# AFE.net
KiCad netlist of a schematic drawn in Altium Designer
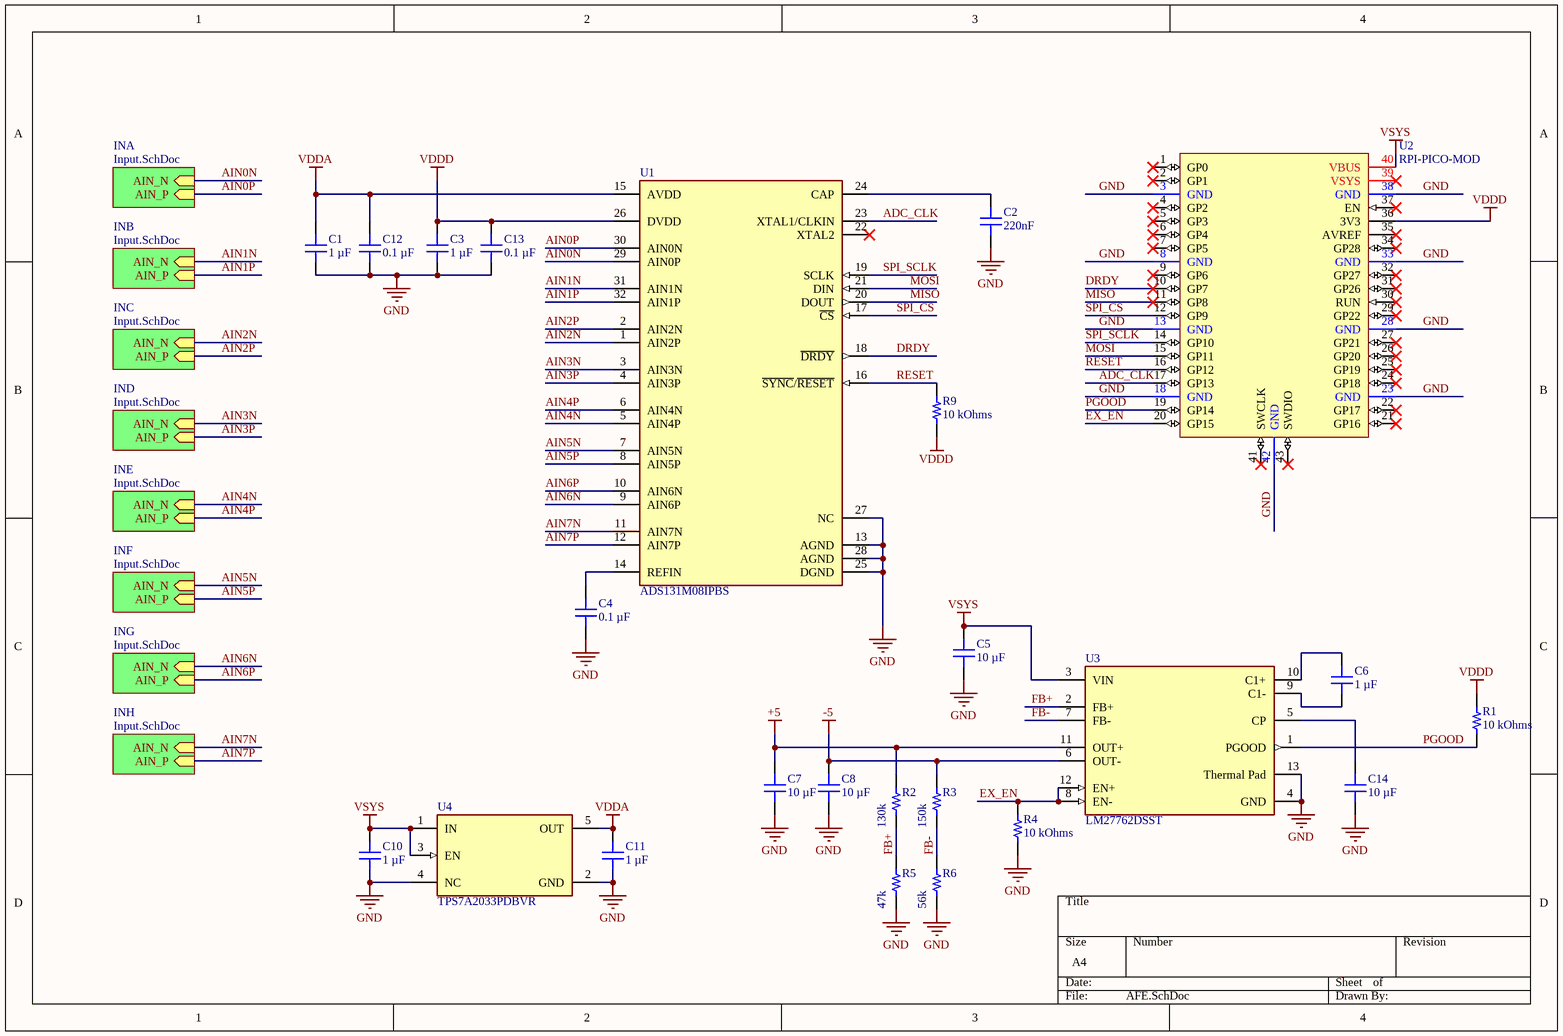
[diagram p0: AFE.SchDoc]

(export (version "E")
  (design (tool "Eeschema 10.0.6"))
  (components
    (comp (ref "C1")
      (value "1 µF")
      (footprint "CAP 0603_1608")
      (description "CAP CER 1UF 16V X7R 0603")
      (fields
        (field (name "PART NUMBER") "C0603C105K4RACAUTO")
        (field (name "CAPACITANCE") "1 µF")
        (field (name "MANUFACTURER") "KEMET")
      )
      (libsource (lib "Celestial Altium Library - altium_library") (part "Capacitor"))
    )
    (comp (ref "C2")
      (value "0.22 µF")
      (footprint "CAP 0603_1608")
      (description "CAP CER 0.22UF 50V X7R 0603")
      (fields
        (field (name "PART NUMBER") "0603BB224K500YT")
        (field (name "CAPACITANCE") "220nF")
        (field (name "MANUFACTURER") "Knowles Novacap")
      )
      (libsource (lib "Celestial Altium Library - altium_library") (part "Capacitor"))
    )
    (comp (ref "C3")
      (value "1 µF")
      (footprint "CAP 0603_1608")
      (description "CAP CER 1UF 16V X7R 0603")
      (fields
        (field (name "PART NUMBER") "C0603C105K4RACAUTO")
        (field (name "CAPACITANCE") "1 µF")
        (field (name "MANUFACTURER") "KEMET")
      )
      (libsource (lib "Celestial Altium Library - altium_library") (part "Capacitor"))
    )
    (comp (ref "C4")
      (value "0.1 µF")
      (footprint "CAP 0603_1608")
      (description "CAP CER 0.1UF 50V X7R 0603")
      (fields
        (field (name "PART NUMBER") "C0603C104K5RAC7411")
        (field (name "CAPACITANCE") "0.1 µF")
        (field (name "MANUFACTURER") "KEMET")
      )
      (libsource (lib "Celestial Altium Library - altium_library") (part "Capacitor"))
    )
    (comp (ref "C5")
      (value "10 µF")
      (footprint "CAP 0805_2012")
      (description "CAP CER 10UF 10V X7S 0805")
      (fields
        (field (name "PART NUMBER") "CL21Y106KPQVPNE")
        (field (name "CAPACITANCE") "10 µF")
        (field (name "MANUFACTURER") "Samsung Electro-Mechanics")
      )
      (libsource (lib "Celestial Altium Library - altium_library") (part "Capacitor"))
    )
    (comp (ref "C6")
      (value "1 µF")
      (footprint "CAP 0603_1608")
      (description "CAP CER 1UF 10V X7R 0603")
      (fields
        (field (name "PART NUMBER") "CC0603KRX7R6BB105")
        (field (name "CAPACITANCE") "1 µF")
        (field (name "MANUFACTURER") "Yageo")
      )
      (libsource (lib "Celestial Altium Library - altium_library") (part "Capacitor"))
    )
    (comp (ref "C7")
      (value "10 µF")
      (footprint "CAP 0805_2012")
      (description "CAP CER 10UF 10V X7S 0805")
      (fields
        (field (name "PART NUMBER") "CL21Y106KPQVPNE")
        (field (name "CAPACITANCE") "10 µF")
        (field (name "MANUFACTURER") "Samsung Electro-Mechanics")
      )
      (libsource (lib "Celestial Altium Library - altium_library") (part "Capacitor"))
    )
    (comp (ref "C8")
      (value "10 µF")
      (footprint "CAP 0805_2012")
      (description "CAP CER 10UF 10V X7S 0805")
      (fields
        (field (name "PART NUMBER") "CL21Y106KPQVPNE")
        (field (name "CAPACITANCE") "10 µF")
        (field (name "MANUFACTURER") "Samsung Electro-Mechanics")
      )
      (libsource (lib "Celestial Altium Library - altium_library") (part "Capacitor"))
    )
    (comp (ref "C10")
      (value "1 µF")
      (footprint "CAP 0603_1608")
      (description "CAP CER 1UF 16V X7R 0603")
      (fields
        (field (name "PART NUMBER") "C0603C105K4RACAUTO")
        (field (name "CAPACITANCE") "1 µF")
        (field (name "MANUFACTURER") "KEMET")
      )
      (libsource (lib "Celestial Altium Library - altium_library") (part "Capacitor"))
    )
    (comp (ref "C11")
      (value "1 µF")
      (footprint "CAP 0603_1608")
      (description "CAP CER 1UF 16V X7R 0603")
      (fields
        (field (name "PART NUMBER") "C0603C105K4RACAUTO")
        (field (name "CAPACITANCE") "1 µF")
        (field (name "MANUFACTURER") "KEMET")
      )
      (libsource (lib "Celestial Altium Library - altium_library") (part "Capacitor"))
    )
    (comp (ref "C12")
      (value "0.1 µF")
      (footprint "CAP 0603_1608")
      (description "CAP CER 0.1UF 50V X7R 0603")
      (fields
        (field (name "PART NUMBER") "C0603C104K5RAC7411")
        (field (name "CAPACITANCE") "0.1 µF")
        (field (name "MANUFACTURER") "KEMET")
      )
      (libsource (lib "Celestial Altium Library - altium_library") (part "Capacitor"))
    )
    (comp (ref "C13")
      (value "0.1 µF")
      (footprint "CAP 0603_1608")
      (description "CAP CER 0.1UF 50V X7R 0603")
      (fields
        (field (name "PART NUMBER") "C0603C104K5RAC7411")
        (field (name "CAPACITANCE") "0.1 µF")
        (field (name "MANUFACTURER") "KEMET")
      )
      (libsource (lib "Celestial Altium Library - altium_library") (part "Capacitor"))
    )
    (comp (ref "C14")
      (value "10 µF")
      (footprint "CAP 0805_2012")
      (description "CAP CER 10UF 10V X7S 0805")
      (fields
        (field (name "PART NUMBER") "CL21Y106KPQVPNE")
        (field (name "CAPACITANCE") "10 µF")
        (field (name "MANUFACTURER") "Samsung Electro-Mechanics")
      )
      (libsource (lib "Celestial Altium Library - altium_library") (part "Capacitor"))
    )
    (comp (ref "R1")
      (value "10 kOhms")
      (footprint "RES 0603_1608")
      (description "RES 10K OHM 0.1% 1/16W 0603")
      (fields
        (field (name "PART NUMBER") "RNCS0603BKE10K0")
        (field (name "MANUFACTURER") "Stackpole Electronics Inc")
      )
      (libsource (lib "Celestial Altium Library - altium_library") (part "Resistor"))
    )
    (comp (ref "R2")
      (value "130k")
      (footprint "RES 0603_1608")
      (description "RES 10K OHM 0.1% 1/16W 0603")
      (fields
        (field (name "PART NUMBER") "RNCS0603BKE10K0")
        (field (name "MANUFACTURER") "Stackpole Electronics Inc")
      )
      (libsource (lib "Celestial Altium Library - altium_library") (part "Resistor"))
    )
    (comp (ref "R3")
      (value "150k")
      (footprint "RES 0603_1608")
      (description "RES 10K OHM 0.1% 1/16W 0603")
      (fields
        (field (name "PART NUMBER") "RNCS0603BKE10K0")
        (field (name "MANUFACTURER") "Stackpole Electronics Inc")
      )
      (libsource (lib "Celestial Altium Library - altium_library") (part "Resistor"))
    )
    (comp (ref "R4")
      (value "10 kOhms")
      (footprint "RES 0603_1608")
      (description "RES 10K OHM 0.1% 1/16W 0603")
      (fields
        (field (name "PART NUMBER") "RNCS0603BKE10K0")
        (field (name "MANUFACTURER") "Stackpole Electronics Inc")
      )
      (libsource (lib "Celestial Altium Library - altium_library") (part "Resistor"))
    )
    (comp (ref "R5")
      (value "47k")
      (footprint "RES 0603_1608")
      (description "RES 10K OHM 0.1% 1/16W 0603")
      (fields
        (field (name "PART NUMBER") "RNCS0603BKE10K0")
        (field (name "MANUFACTURER") "Stackpole Electronics Inc")
      )
      (libsource (lib "Celestial Altium Library - altium_library") (part "Resistor"))
    )
    (comp (ref "R6")
      (value "56k")
      (footprint "RES 0603_1608")
      (description "RES 10K OHM 0.1% 1/16W 0603")
      (fields
        (field (name "PART NUMBER") "RNCS0603BKE10K0")
        (field (name "MANUFACTURER") "Stackpole Electronics Inc")
      )
      (libsource (lib "Celestial Altium Library - altium_library") (part "Resistor"))
    )
    (comp (ref "R9")
      (value "10 kOhms")
      (footprint "RES 0603_1608")
      (description "RES 10K OHM 0.1% 1/16W 0603")
      (fields
        (field (name "PART NUMBER") "RNCS0603BKE10K0")
        (field (name "MANUFACTURER") "Stackpole Electronics Inc")
      )
      (libsource (lib "Celestial Altium Library - altium_library") (part "Resistor"))
    )
    (comp (ref "U1")
      (value "ADS131M08IPBS")
      (footprint "FP-PBS0032A-MFG")
      (description "8 CHANNEL 24 BIT SIMULTANEOUS SA")
      (libsource (lib "Altium Content Vault") (part "d3235cd83c76fd1a87a5b9f7ea79bfa"))
    )
    (comp (ref "U2")
      (value "RPI-PICO-MOD")
      (footprint "RPI-PICO-MOD")
      (description "RASPBERRY PI PICO RP2040 BOARD")
      (fields
        (field (name "MANUFACTURER PART NO") "SC0915")
        (field (name "MANUFACTURER") "Raspberry Pi Foundation")
      )
      (libsource (lib "CLES_FACIL") (part "RPI-PICO-MOD"))
    )
    (comp (ref "U3")
      (value "LM27762DSST")
      (footprint "FP-DSS0012B-MFG")
      (description "Switched Capacitor Converter, 0.25A, 2200kHz Switching Freq-Max, PDSO12")
      (libsource (lib "CLES_FACIL") (part "8596a2cad692279f3036c687582cd61"))
    )
    (comp (ref "U4")
      (value "TPS7A2033PDBVR")
      (footprint "FP-DBV0005A-MFG")
      (description "IC REG LINEAR 3.3V 300MA SOT23-5")
      (libsource (lib "Altium Content Vault") (part "76aa7ad0ceb1012e0d85aeafc53095f"))
    )
  )
  (nets
    (net (code "1") (name "+5") (class "Default")
      (node (ref "C7") (pin "2") (pinfunction "2_2") (pintype "passive"))
      (node (ref "R2") (pin "2") (pinfunction "2_2") (pintype "passive"))
      (node (ref "U3") (pin "11") (pinfunction "OUT+_11") (pintype "power_in"))
    )
    (net (code "2") (name "-5") (class "Default")
      (node (ref "C8") (pin "2") (pinfunction "2_2") (pintype "passive"))
      (node (ref "R3") (pin "2") (pinfunction "2_2") (pintype "passive"))
      (node (ref "U3") (pin "6") (pinfunction "OUT-_6") (pintype "power_in"))
    )
    (net (code "3") (name "/ADC_CLK") (class "Default")
      (node (ref "U1") (pin "23") (pinfunction "XTAL1/CLKIN_23") (pintype "passive"))
      (node (ref "U2") (pin "17") (pinfunction "GP13_17") (pintype "bidirectional"))
    )
    (net (code "4") (name "/AIN0N") (class "Default")
      (node (ref "U1") (pin "29") (pinfunction "AIN0P_29") (pintype "passive"))
    )
    (net (code "5") (name "/AIN0P") (class "Default")
      (node (ref "U1") (pin "30") (pinfunction "AIN0N_30") (pintype "passive"))
    )
    (net (code "6") (name "/AIN1N") (class "Default")
      (node (ref "U1") (pin "31") (pinfunction "AIN1N_31") (pintype "passive"))
    )
    (net (code "7") (name "/AIN1P") (class "Default")
      (node (ref "U1") (pin "32") (pinfunction "AIN1P_32") (pintype "passive"))
    )
    (net (code "8") (name "/AIN2N") (class "Default")
      (node (ref "U1") (pin "1") (pinfunction "AIN2P_1") (pintype "passive"))
    )
    (net (code "9") (name "/AIN2P") (class "Default")
      (node (ref "U1") (pin "2") (pinfunction "AIN2N_2") (pintype "passive"))
    )
    (net (code "10") (name "/AIN3N") (class "Default")
      (node (ref "U1") (pin "3") (pinfunction "AIN3N_3") (pintype "passive"))
    )
    (net (code "11") (name "/AIN3P") (class "Default")
      (node (ref "U1") (pin "4") (pinfunction "AIN3P_4") (pintype "passive"))
    )
    (net (code "12") (name "/AIN4N") (class "Default")
      (node (ref "U1") (pin "5") (pinfunction "AIN4P_5") (pintype "passive"))
    )
    (net (code "13") (name "/AIN4P") (class "Default")
      (node (ref "U1") (pin "6") (pinfunction "AIN4N_6") (pintype "passive"))
    )
    (net (code "14") (name "/AIN5N") (class "Default")
      (node (ref "U1") (pin "7") (pinfunction "AIN5N_7") (pintype "passive"))
    )
    (net (code "15") (name "/AIN5P") (class "Default")
      (node (ref "U1") (pin "8") (pinfunction "AIN5P_8") (pintype "passive"))
    )
    (net (code "16") (name "/AIN6N") (class "Default")
      (node (ref "U1") (pin "9") (pinfunction "AIN6P_9") (pintype "passive"))
    )
    (net (code "17") (name "/AIN6P") (class "Default")
      (node (ref "U1") (pin "10") (pinfunction "AIN6N_10") (pintype "passive"))
    )
    (net (code "18") (name "/AIN7N") (class "Default")
      (node (ref "U1") (pin "11") (pinfunction "AIN7N_11") (pintype "passive"))
    )
    (net (code "19") (name "/AIN7P") (class "Default")
      (node (ref "U1") (pin "12") (pinfunction "AIN7P_12") (pintype "passive"))
    )
    (net (code "20") (name "/DRDY") (class "Default")
      (node (ref "U1") (pin "18") (pinfunction "~{DRDY}_18") (pintype "output"))
      (node (ref "U2") (pin "10") (pinfunction "GP7_10") (pintype "bidirectional"))
    )
    (net (code "21") (name "/EX_EN") (class "Default")
      (node (ref "R4") (pin "2") (pinfunction "2_2") (pintype "passive"))
      (node (ref "U2") (pin "20") (pinfunction "GP15_20") (pintype "bidirectional"))
      (node (ref "U3") (pin "12") (pinfunction "EN+_12") (pintype "input"))
      (node (ref "U3") (pin "8") (pinfunction "EN-_8") (pintype "input"))
    )
    (net (code "22") (name "/FB+") (class "Default")
      (node (ref "R2") (pin "1") (pinfunction "1_1") (pintype "passive"))
      (node (ref "R5") (pin "2") (pinfunction "2_2") (pintype "passive"))
      (node (ref "U3") (pin "2") (pinfunction "FB+_2") (pintype "power_in"))
    )
    (net (code "23") (name "/FB-") (class "Default")
      (node (ref "R3") (pin "1") (pinfunction "1_1") (pintype "passive"))
      (node (ref "R6") (pin "2") (pinfunction "2_2") (pintype "passive"))
      (node (ref "U3") (pin "7") (pinfunction "FB-_7") (pintype "power_in"))
    )
    (net (code "24") (name "/MISO") (class "Default")
      (node (ref "U1") (pin "20") (pinfunction "DOUT_20") (pintype "output"))
      (node (ref "U2") (pin "11") (pinfunction "GP8_11") (pintype "bidirectional"))
    )
    (net (code "25") (name "/MOSI") (class "Default")
      (node (ref "U1") (pin "21") (pinfunction "DIN_21") (pintype "input"))
      (node (ref "U2") (pin "15") (pinfunction "GP11_15") (pintype "bidirectional"))
    )
    (net (code "26") (name "/PGOOD") (class "Default")
      (node (ref "R1") (pin "1") (pinfunction "1_1") (pintype "passive"))
      (node (ref "U2") (pin "19") (pinfunction "GP14_19") (pintype "bidirectional"))
      (node (ref "U3") (pin "1") (pinfunction "PGOOD_1") (pintype "output"))
    )
    (net (code "27") (name "/RESET") (class "Default")
      (node (ref "R9") (pin "2") (pinfunction "2_2") (pintype "passive"))
      (node (ref "U1") (pin "16") (pinfunction "~{SYNC}/~{RESET}_16") (pintype "input"))
      (node (ref "U2") (pin "16") (pinfunction "GP12_16") (pintype "bidirectional"))
    )
    (net (code "28") (name "/SPI_CS") (class "Default")
      (node (ref "U1") (pin "17") (pinfunction "~{CS}_17") (pintype "input"))
      (node (ref "U2") (pin "12") (pinfunction "GP9_12") (pintype "bidirectional"))
    )
    (net (code "29") (name "/SPI_SCLK") (class "Default")
      (node (ref "U1") (pin "19") (pinfunction "SCLK_19") (pintype "input"))
      (node (ref "U2") (pin "14") (pinfunction "GP10_14") (pintype "bidirectional"))
    )
    (net (code "30") (name "GND") (class "Default")
      (node (ref "C1") (pin "1") (pinfunction "1_1") (pintype "passive"))
      (node (ref "C10") (pin "1") (pinfunction "1_1") (pintype "passive"))
      (node (ref "C11") (pin "1") (pinfunction "1_1") (pintype "passive"))
      (node (ref "C12") (pin "1") (pinfunction "1_1") (pintype "passive"))
      (node (ref "C13") (pin "1") (pinfunction "1_1") (pintype "passive"))
      (node (ref "C14") (pin "1") (pinfunction "1_1") (pintype "passive"))
      (node (ref "C2") (pin "1") (pinfunction "1_1") (pintype "passive"))
      (node (ref "C3") (pin "1") (pinfunction "1_1") (pintype "passive"))
      (node (ref "C4") (pin "1") (pinfunction "1_1") (pintype "passive"))
      (node (ref "C5") (pin "1") (pinfunction "1_1") (pintype "passive"))
      (node (ref "C7") (pin "1") (pinfunction "1_1") (pintype "passive"))
      (node (ref "C8") (pin "1") (pinfunction "1_1") (pintype "passive"))
      (node (ref "R4") (pin "1") (pinfunction "1_1") (pintype "passive"))
      (node (ref "R5") (pin "1") (pinfunction "1_1") (pintype "passive"))
      (node (ref "R6") (pin "1") (pinfunction "1_1") (pintype "passive"))
      (node (ref "U1") (pin "13") (pinfunction "AGND_13") (pintype "power_in"))
      (node (ref "U1") (pin "25") (pinfunction "DGND_25") (pintype "power_in"))
      (node (ref "U1") (pin "27") (pinfunction "NC_27") (pintype "passive"))
      (node (ref "U1") (pin "28") (pinfunction "AGND_28") (pintype "power_in"))
      (node (ref "U2") (pin "13") (pinfunction "GND_13") (pintype "power_in"))
      (node (ref "U2") (pin "18") (pinfunction "GND_18") (pintype "power_in"))
      (node (ref "U2") (pin "23") (pinfunction "GND_23") (pintype "power_in"))
      (node (ref "U2") (pin "28") (pinfunction "GND_28") (pintype "power_in"))
      (node (ref "U2") (pin "3") (pinfunction "GND_3") (pintype "power_in"))
      (node (ref "U2") (pin "33") (pinfunction "GND_33") (pintype "power_in"))
      (node (ref "U2") (pin "38") (pinfunction "GND_38") (pintype "power_in"))
      (node (ref "U2") (pin "42") (pinfunction "GND_42") (pintype "power_in"))
      (node (ref "U2") (pin "8") (pinfunction "GND_8") (pintype "power_in"))
      (node (ref "U3") (pin "13") (pinfunction "Thermal_Pad_13") (pintype "power_in"))
      (node (ref "U3") (pin "4") (pinfunction "GND_4") (pintype "power_in"))
      (node (ref "U4") (pin "2") (pinfunction "GND_2") (pintype "power_in"))
      (node (ref "U4") (pin "4") (pinfunction "NC_4") (pintype "passive"))
    )
    (net (code "31") (name "Net-(U1-CAP)") (class "Default")
      (node (ref "C2") (pin "2") (pinfunction "2_2") (pintype "passive"))
      (node (ref "U1") (pin "24") (pinfunction "CAP_24") (pintype "passive"))
    )
    (net (code "32") (name "Net-(U1-REFIN)") (class "Default")
      (node (ref "C4") (pin "2") (pinfunction "2_2") (pintype "passive"))
      (node (ref "U1") (pin "14") (pinfunction "REFIN_14") (pintype "passive"))
    )
    (net (code "33") (name "Net-(U3-C1+)") (class "Default")
      (node (ref "C6") (pin "2") (pinfunction "2_2") (pintype "passive"))
      (node (ref "U3") (pin "10") (pinfunction "C1+_10") (pintype "power_in"))
    )
    (net (code "34") (name "Net-(U3-C1-)") (class "Default")
      (node (ref "C6") (pin "1") (pinfunction "1_1") (pintype "passive"))
      (node (ref "U3") (pin "9") (pinfunction "C1-_9") (pintype "power_in"))
    )
    (net (code "35") (name "Net-(U3-CP)") (class "Default")
      (node (ref "C14") (pin "2") (pinfunction "2_2") (pintype "passive"))
      (node (ref "U3") (pin "5") (pinfunction "CP_5") (pintype "power_in"))
    )
    (net (code "36") (name "VDDA") (class "Default")
      (node (ref "C1") (pin "2") (pinfunction "2_2") (pintype "passive"))
      (node (ref "C11") (pin "2") (pinfunction "2_2") (pintype "passive"))
      (node (ref "C12") (pin "2") (pinfunction "2_2") (pintype "passive"))
      (node (ref "U1") (pin "15") (pinfunction "AVDD_15") (pintype "power_in"))
      (node (ref "U4") (pin "5") (pinfunction "OUT_5") (pintype "passive"))
    )
    (net (code "37") (name "VDDD") (class "Default")
      (node (ref "C13") (pin "2") (pinfunction "2_2") (pintype "passive"))
      (node (ref "C3") (pin "2") (pinfunction "2_2") (pintype "passive"))
      (node (ref "R1") (pin "2") (pinfunction "2_2") (pintype "passive"))
      (node (ref "R9") (pin "1") (pinfunction "1_1") (pintype "passive"))
      (node (ref "U1") (pin "26") (pinfunction "DVDD_26") (pintype "power_in"))
      (node (ref "U2") (pin "36") (pinfunction "3V3_36") (pintype "power_in"))
    )
    (net (code "38") (name "VSYS") (class "Default")
      (node (ref "C10") (pin "2") (pinfunction "2_2") (pintype "passive"))
      (node (ref "C5") (pin "2") (pinfunction "2_2") (pintype "passive"))
      (node (ref "U2") (pin "40") (pinfunction "VBUS_40") (pintype "power_in"))
      (node (ref "U3") (pin "3") (pinfunction "VIN_3") (pintype "power_in"))
      (node (ref "U4") (pin "1") (pinfunction "IN_1") (pintype "power_in"))
      (node (ref "U4") (pin "3") (pinfunction "EN_3") (pintype "input"))
    )
    (net (code "39") (name "unconnected-(U1-XTAL2-Pad22)") (class "Default")
      (node (ref "U1") (pin "22") (pinfunction "XTAL2_22") (pintype "passive+no_connect"))
    )
    (net (code "40") (name "unconnected-(U2-AVREF-Pad35)") (class "Default")
      (node (ref "U2") (pin "35") (pinfunction "AVREF_35") (pintype "power_in+no_connect"))
    )
    (net (code "41") (name "unconnected-(U2-EN-Pad37)") (class "Default")
      (node (ref "U2") (pin "37") (pinfunction "EN_37") (pintype "input+no_connect"))
    )
    (net (code "42") (name "unconnected-(U2-GP0-Pad1)") (class "Default")
      (node (ref "U2") (pin "1") (pinfunction "GP0_1") (pintype "bidirectional+no_connect"))
    )
    (net (code "43") (name "unconnected-(U2-GP1-Pad2)") (class "Default")
      (node (ref "U2") (pin "2") (pinfunction "GP1_2") (pintype "bidirectional+no_connect"))
    )
    (net (code "44") (name "unconnected-(U2-GP2-Pad4)") (class "Default")
      (node (ref "U2") (pin "4") (pinfunction "GP2_4") (pintype "bidirectional+no_connect"))
    )
    (net (code "45") (name "unconnected-(U2-GP3-Pad5)") (class "Default")
      (node (ref "U2") (pin "5") (pinfunction "GP3_5") (pintype "bidirectional+no_connect"))
    )
    (net (code "46") (name "unconnected-(U2-GP4-Pad6)") (class "Default")
      (node (ref "U2") (pin "6") (pinfunction "GP4_6") (pintype "bidirectional+no_connect"))
    )
    (net (code "47") (name "unconnected-(U2-GP5-Pad7)") (class "Default")
      (node (ref "U2") (pin "7") (pinfunction "GP5_7") (pintype "bidirectional+no_connect"))
    )
    (net (code "48") (name "unconnected-(U2-GP6-Pad9)") (class "Default")
      (node (ref "U2") (pin "9") (pinfunction "GP6_9") (pintype "bidirectional+no_connect"))
    )
    (net (code "49") (name "unconnected-(U2-GP16-Pad21)") (class "Default")
      (node (ref "U2") (pin "21") (pinfunction "GP16_21") (pintype "bidirectional+no_connect"))
    )
    (net (code "50") (name "unconnected-(U2-GP17-Pad22)") (class "Default")
      (node (ref "U2") (pin "22") (pinfunction "GP17_22") (pintype "bidirectional+no_connect"))
    )
    (net (code "51") (name "unconnected-(U2-GP18-Pad24)") (class "Default")
      (node (ref "U2") (pin "24") (pinfunction "GP18_24") (pintype "bidirectional+no_connect"))
    )
    (net (code "52") (name "unconnected-(U2-GP19-Pad25)") (class "Default")
      (node (ref "U2") (pin "25") (pinfunction "GP19_25") (pintype "bidirectional+no_connect"))
    )
    (net (code "53") (name "unconnected-(U2-GP20-Pad26)") (class "Default")
      (node (ref "U2") (pin "26") (pinfunction "GP20_26") (pintype "bidirectional+no_connect"))
    )
    (net (code "54") (name "unconnected-(U2-GP21-Pad27)") (class "Default")
      (node (ref "U2") (pin "27") (pinfunction "GP21_27") (pintype "bidirectional+no_connect"))
    )
    (net (code "55") (name "unconnected-(U2-GP22-Pad29)") (class "Default")
      (node (ref "U2") (pin "29") (pinfunction "GP22_29") (pintype "bidirectional+no_connect"))
    )
    (net (code "56") (name "unconnected-(U2-GP26-Pad31)") (class "Default")
      (node (ref "U2") (pin "31") (pinfunction "GP26_31") (pintype "bidirectional+no_connect"))
    )
    (net (code "57") (name "unconnected-(U2-GP27-Pad32)") (class "Default")
      (node (ref "U2") (pin "32") (pinfunction "GP27_32") (pintype "bidirectional+no_connect"))
    )
    (net (code "58") (name "unconnected-(U2-GP28-Pad34)") (class "Default")
      (node (ref "U2") (pin "34") (pinfunction "GP28_34") (pintype "bidirectional+no_connect"))
    )
    (net (code "59") (name "unconnected-(U2-RUN-Pad30)") (class "Default")
      (node (ref "U2") (pin "30") (pinfunction "RUN_30") (pintype "input+no_connect"))
    )
    (net (code "60") (name "unconnected-(U2-SWCLK-Pad41)") (class "Default")
      (node (ref "U2") (pin "41") (pinfunction "SWCLK_41") (pintype "bidirectional+no_connect"))
    )
    (net (code "61") (name "unconnected-(U2-SWDIO-Pad43)") (class "Default")
      (node (ref "U2") (pin "43") (pinfunction "SWDIO_43") (pintype "bidirectional+no_connect"))
    )
    (net (code "62") (name "unconnected-(U2-VSYS-Pad39)") (class "Default")
      (node (ref "U2") (pin "39") (pinfunction "VSYS_39") (pintype "power_in+no_connect"))
    )
  )
)
